# OpAmp.net
KiCad netlist of a schematic drawn in Altium Designer
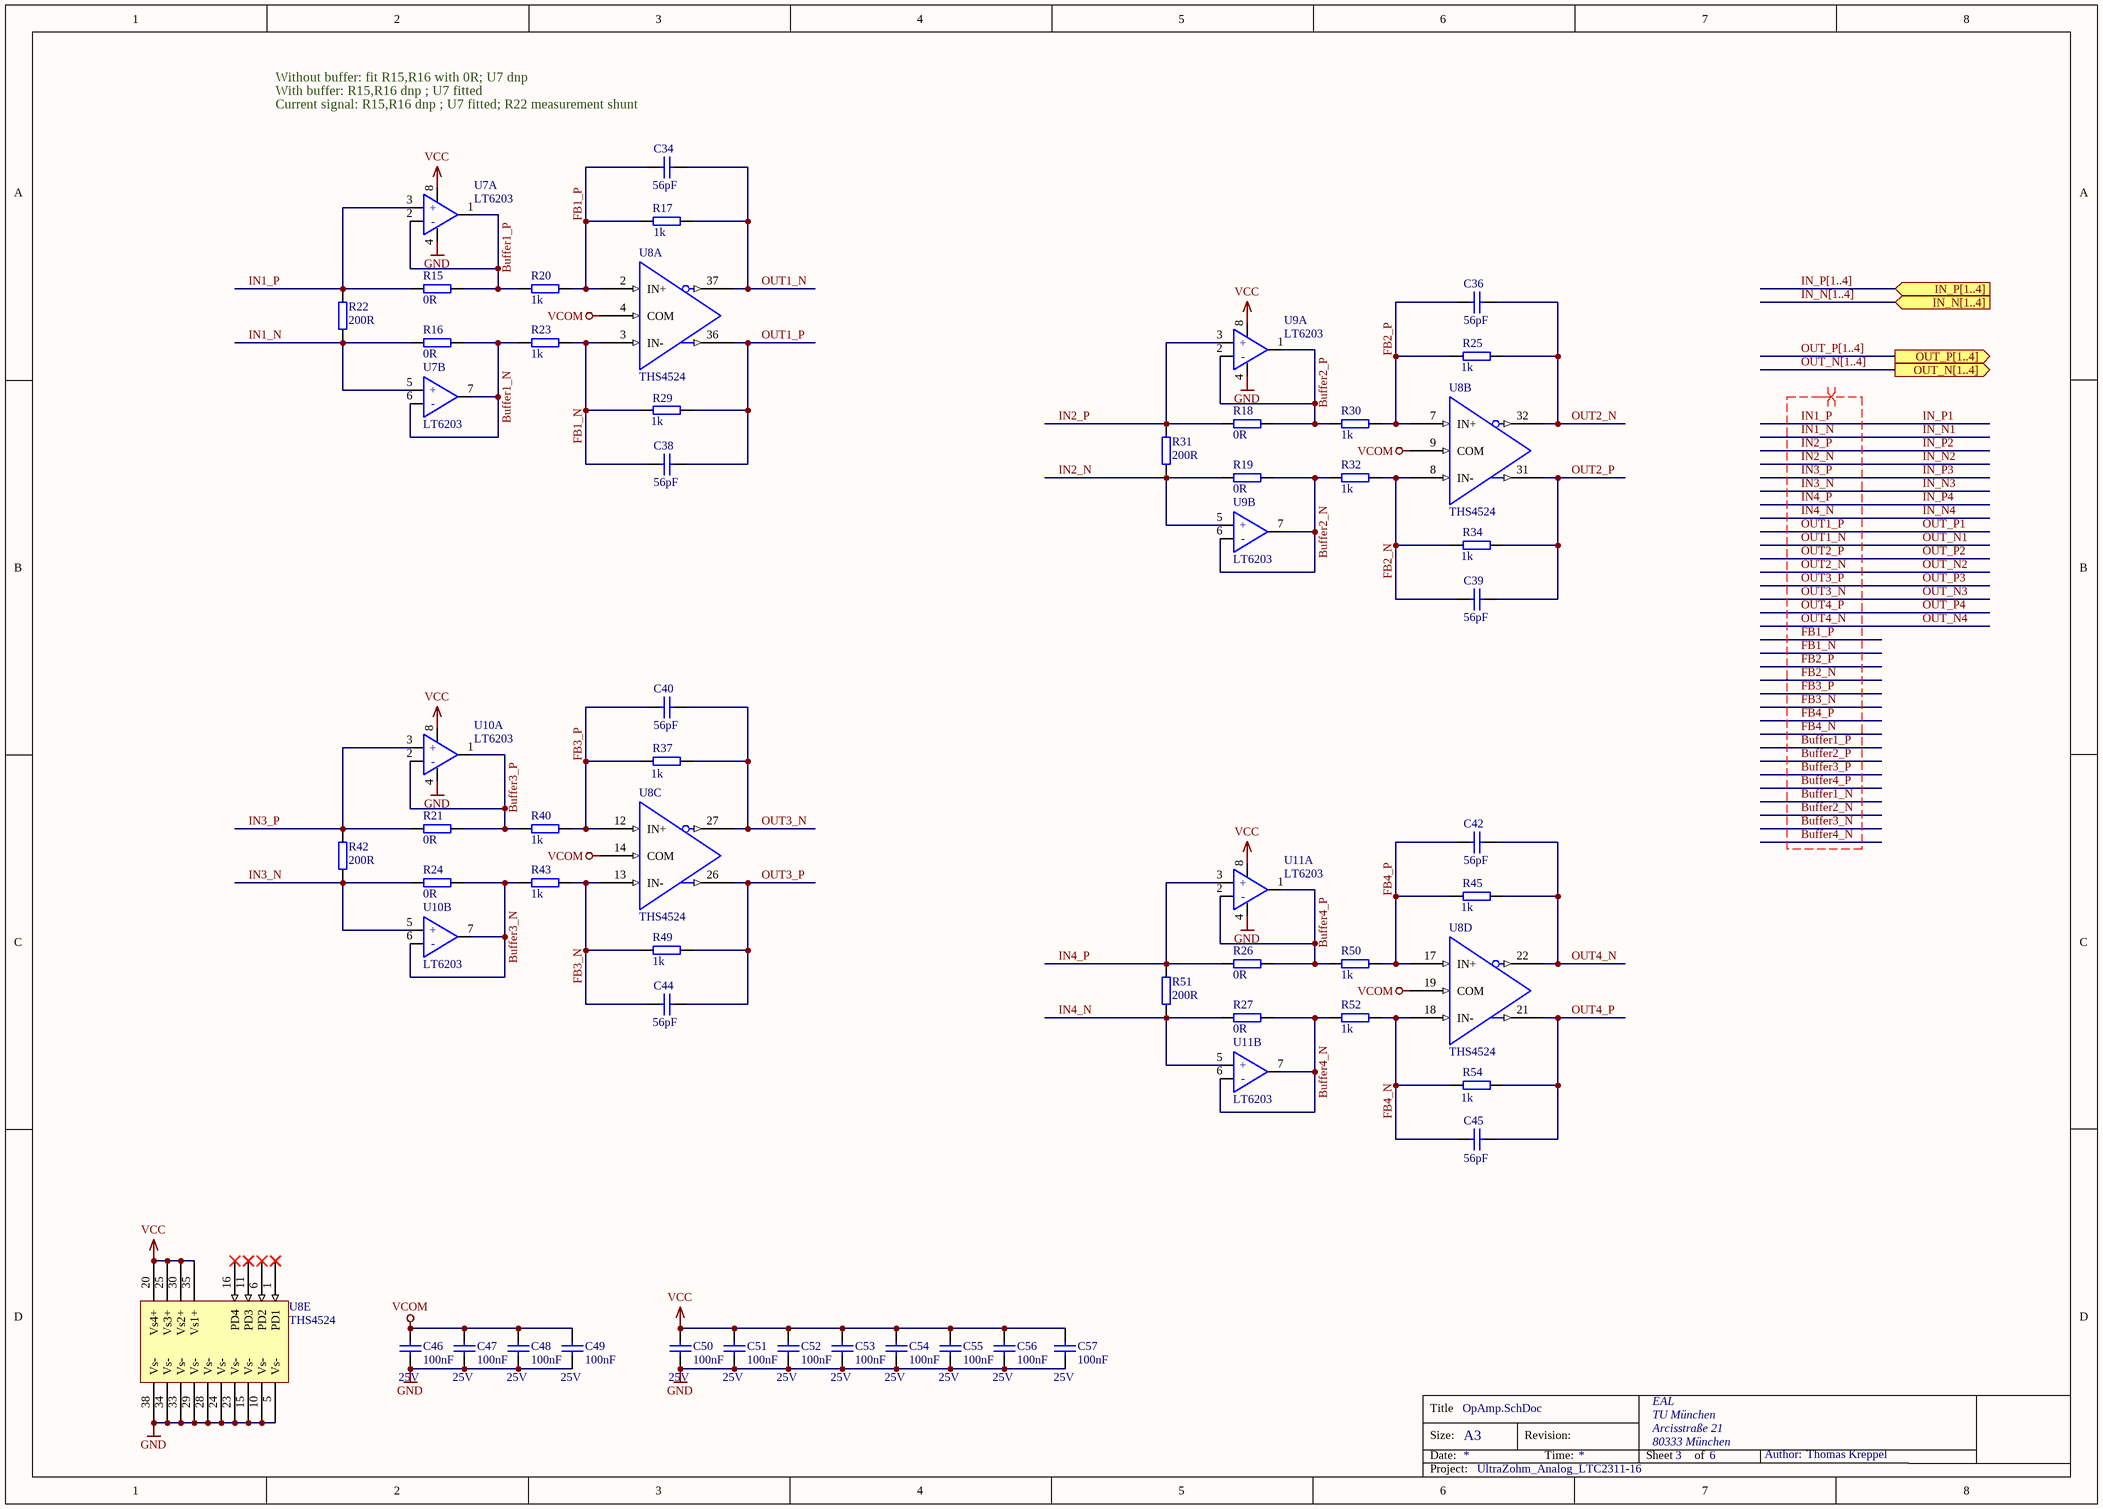
[diagram p0: OpAmp.SchDoc]

(export (version "E")
  (design (tool "Eeschema 10.0.6"))
  (components
    (comp (ref "C34")
      (value "56pF")
      (footprint "CAPC1608X07N")
      (fields
        (field (name "MF") "Vishay")
        (field (name "MPN") "VJ0603A560JXACW1BC")
        (field (name "VOLTAGE") "50V")
      )
      (libsource (lib "UltraZohm_ADC") (part "Cap_0603"))
    )
    (comp (ref "C36")
      (value "56pF")
      (footprint "CAPC1608X07N")
      (fields
        (field (name "MF") "Vishay")
        (field (name "MPN") "VJ0603A560JXACW1BC")
        (field (name "VOLTAGE") "50V")
      )
      (libsource (lib "UltraZohm_ADC") (part "Cap_0603"))
    )
    (comp (ref "C38")
      (value "56pF")
      (footprint "CAPC1608X07N")
      (fields
        (field (name "MF") "Vishay")
        (field (name "MPN") "VJ0603A560JXACW1BC")
        (field (name "VOLTAGE") "50V")
      )
      (libsource (lib "UltraZohm_ADC") (part "Cap_0603"))
    )
    (comp (ref "C39")
      (value "56pF")
      (footprint "CAPC1608X07N")
      (fields
        (field (name "MF") "Vishay")
        (field (name "MPN") "VJ0603A560JXACW1BC")
        (field (name "VOLTAGE") "50V")
      )
      (libsource (lib "UltraZohm_ADC") (part "Cap_0603"))
    )
    (comp (ref "C40")
      (value "56pF")
      (footprint "CAPC1608X07N")
      (fields
        (field (name "MF") "Vishay")
        (field (name "MPN") "VJ0603A560JXACW1BC")
        (field (name "VOLTAGE") "50V")
      )
      (libsource (lib "UltraZohm_ADC") (part "Cap_0603"))
    )
    (comp (ref "C42")
      (value "56pF")
      (footprint "CAPC1608X07N")
      (fields
        (field (name "MF") "Vishay")
        (field (name "MPN") "VJ0603A560JXACW1BC")
        (field (name "VOLTAGE") "50V")
      )
      (libsource (lib "UltraZohm_ADC") (part "Cap_0603"))
    )
    (comp (ref "C44")
      (value "56pF")
      (footprint "CAPC1608X07N")
      (fields
        (field (name "MF") "Vishay")
        (field (name "MPN") "VJ0603A560JXACW1BC")
        (field (name "VOLTAGE") "50V")
      )
      (libsource (lib "UltraZohm_ADC") (part "Cap_0603"))
    )
    (comp (ref "C45")
      (value "56pF")
      (footprint "CAPC1608X07N")
      (fields
        (field (name "MF") "Vishay")
        (field (name "MPN") "VJ0603A560JXACW1BC")
        (field (name "VOLTAGE") "50V")
      )
      (libsource (lib "UltraZohm_ADC") (part "Cap_0603"))
    )
    (comp (ref "C46")
      (value "100nF")
      (footprint "CAPC1608X07N")
      (fields (field (name "MF") "Würth") (field (name "MPN") "885012206071") (field (name "VOLTAGE") "25V"))
      (libsource (lib "UltraZohm_ADC") (part "Cap_0603"))
    )
    (comp (ref "C47")
      (value "100nF")
      (footprint "CAPC1608X07N")
      (fields (field (name "MF") "Würth") (field (name "MPN") "885012206071") (field (name "VOLTAGE") "25V"))
      (libsource (lib "UltraZohm_ADC") (part "Cap_0603"))
    )
    (comp (ref "C48")
      (value "100nF")
      (footprint "CAPC1608X07N")
      (fields (field (name "MF") "Würth") (field (name "MPN") "885012206071") (field (name "VOLTAGE") "25V"))
      (libsource (lib "UltraZohm_ADC") (part "Cap_0603"))
    )
    (comp (ref "C49")
      (value "100nF")
      (footprint "CAPC1608X07N")
      (fields (field (name "MF") "Würth") (field (name "MPN") "885012206071") (field (name "VOLTAGE") "25V"))
      (libsource (lib "UltraZohm_ADC") (part "Cap_0603"))
    )
    (comp (ref "C50")
      (value "100nF")
      (footprint "CAPC1608X07N")
      (fields (field (name "MF") "Würth") (field (name "MPN") "885012206071") (field (name "VOLTAGE") "25V"))
      (libsource (lib "UltraZohm_ADC") (part "Cap_0603"))
    )
    (comp (ref "C51")
      (value "100nF")
      (footprint "CAPC1608X07N")
      (fields (field (name "MF") "Würth") (field (name "MPN") "885012206071") (field (name "VOLTAGE") "25V"))
      (libsource (lib "UltraZohm_ADC") (part "Cap_0603"))
    )
    (comp (ref "C52")
      (value "100nF")
      (footprint "CAPC1608X07N")
      (fields (field (name "MF") "Würth") (field (name "MPN") "885012206071") (field (name "VOLTAGE") "25V"))
      (libsource (lib "UltraZohm_ADC") (part "Cap_0603"))
    )
    (comp (ref "C53")
      (value "100nF")
      (footprint "CAPC1608X07N")
      (fields (field (name "MF") "Würth") (field (name "MPN") "885012206071") (field (name "VOLTAGE") "25V"))
      (libsource (lib "UltraZohm_ADC") (part "Cap_0603"))
    )
    (comp (ref "C54")
      (value "100nF")
      (footprint "CAPC1608X07N")
      (fields (field (name "MF") "Würth") (field (name "MPN") "885012206071") (field (name "VOLTAGE") "25V"))
      (libsource (lib "UltraZohm_ADC") (part "Cap_0603"))
    )
    (comp (ref "C55")
      (value "100nF")
      (footprint "CAPC1608X07N")
      (fields (field (name "MF") "Würth") (field (name "MPN") "885012206071") (field (name "VOLTAGE") "25V"))
      (libsource (lib "UltraZohm_ADC") (part "Cap_0603"))
    )
    (comp (ref "C56")
      (value "100nF")
      (footprint "CAPC1608X07N")
      (fields (field (name "MF") "Würth") (field (name "MPN") "885012206071") (field (name "VOLTAGE") "25V"))
      (libsource (lib "UltraZohm_ADC") (part "Cap_0603"))
    )
    (comp (ref "C57")
      (value "100nF")
      (footprint "CAPC1608X07N")
      (fields (field (name "MF") "Würth") (field (name "MPN") "885012206071") (field (name "VOLTAGE") "25V"))
      (libsource (lib "UltraZohm_ADC") (part "Cap_0603"))
    )
    (comp (ref "R15")
      (value "0R")
      (footprint "RESC1608X06N")
      (fields (field (name "MF") "Vishay / Dale") (field (name "MPN") "CRCW06030000Z0EBC"))
      (libsource (lib "UltraZohm_ADC") (part "R_0603"))
    )
    (comp (ref "R16")
      (value "0R")
      (footprint "RESC1608X06N")
      (fields (field (name "MF") "Vishay / Dale") (field (name "MPN") "CRCW06030000Z0EBC"))
      (libsource (lib "UltraZohm_ADC") (part "R_0603"))
    )
    (comp (ref "R17")
      (value "1k")
      (footprint "RESC1608X06N")
      (fields (field (name "MF") "Vishay / Dale") (field (name "MPN") "CRCW06031K00JNEAC"))
      (libsource (lib "UltraZohm_ADC") (part "R_0603"))
    )
    (comp (ref "R18")
      (value "0R")
      (footprint "RESC1608X06N")
      (fields (field (name "MF") "Vishay / Dale") (field (name "MPN") "CRCW06030000Z0EBC"))
      (libsource (lib "UltraZohm_ADC") (part "R_0603"))
    )
    (comp (ref "R19")
      (value "0R")
      (footprint "RESC1608X06N")
      (fields (field (name "MF") "Vishay / Dale") (field (name "MPN") "CRCW06030000Z0EBC"))
      (libsource (lib "UltraZohm_ADC") (part "R_0603"))
    )
    (comp (ref "R20")
      (value "1k")
      (footprint "RESC1608X06N")
      (fields (field (name "MF") "Vishay / Dale") (field (name "MPN") "CRCW06031K00JNEAC"))
      (libsource (lib "UltraZohm_ADC") (part "R_0603"))
    )
    (comp (ref "R21")
      (value "0R")
      (footprint "RESC1608X06N")
      (fields (field (name "MF") "Vishay / Dale") (field (name "MPN") "CRCW06030000Z0EBC"))
      (libsource (lib "UltraZohm_ADC") (part "R_0603"))
    )
    (comp (ref "R22")
      (value "200R")
      (footprint "RESC3216X65N")
      (description "WID SMD 1M 5% 0,25W")
      (fields
        (field (name "TOLERANCE") "5%")
        (field (name "MF") "AECOL/Ohmite")
        (field (name "CREATED") "2018_07_20_AGeiger")
      )
      (libsource (lib "UltraZOhm_CarrierBoard") (part "R_1206"))
    )
    (comp (ref "R23")
      (value "1k")
      (footprint "RESC1608X06N")
      (fields (field (name "MF") "Vishay / Dale") (field (name "MPN") "CRCW06031K00JNEAC"))
      (libsource (lib "UltraZohm_ADC") (part "R_0603"))
    )
    (comp (ref "R24")
      (value "0R")
      (footprint "RESC1608X06N")
      (fields (field (name "MF") "Vishay / Dale") (field (name "MPN") "CRCW06030000Z0EBC"))
      (libsource (lib "UltraZohm_ADC") (part "R_0603"))
    )
    (comp (ref "R25")
      (value "1k")
      (footprint "RESC1608X06N")
      (fields (field (name "MF") "Vishay / Dale") (field (name "MPN") "CRCW06031K00JNEAC"))
      (libsource (lib "UltraZohm_ADC") (part "R_0603"))
    )
    (comp (ref "R26")
      (value "0R")
      (footprint "RESC1608X06N")
      (fields (field (name "MF") "Vishay / Dale") (field (name "MPN") "CRCW06030000Z0EBC"))
      (libsource (lib "UltraZohm_ADC") (part "R_0603"))
    )
    (comp (ref "R27")
      (value "0R")
      (footprint "RESC1608X06N")
      (fields (field (name "MF") "Vishay / Dale") (field (name "MPN") "CRCW06030000Z0EBC"))
      (libsource (lib "UltraZohm_ADC") (part "R_0603"))
    )
    (comp (ref "R29")
      (value "1k")
      (footprint "RESC1608X06N")
      (fields (field (name "MF") "Vishay / Dale") (field (name "MPN") "CRCW06031K00JNEAC"))
      (libsource (lib "UltraZohm_ADC") (part "R_0603"))
    )
    (comp (ref "R30")
      (value "1k")
      (footprint "RESC1608X06N")
      (fields (field (name "MF") "Vishay / Dale") (field (name "MPN") "CRCW06031K00JNEAC"))
      (libsource (lib "UltraZohm_ADC") (part "R_0603"))
    )
    (comp (ref "R31")
      (value "200R")
      (footprint "RESC3216X65N")
      (description "WID SMD 1M 5% 0,25W")
      (fields
        (field (name "TOLERANCE") "5%")
        (field (name "MF") "AECOL/Ohmite")
        (field (name "CREATED") "2018_07_20_AGeiger")
      )
      (libsource (lib "UltraZOhm_CarrierBoard") (part "R_1206"))
    )
    (comp (ref "R32")
      (value "1k")
      (footprint "RESC1608X06N")
      (fields (field (name "MF") "Vishay / Dale") (field (name "MPN") "CRCW06031K00JNEAC"))
      (libsource (lib "UltraZohm_ADC") (part "R_0603"))
    )
    (comp (ref "R34")
      (value "1k")
      (footprint "RESC1608X06N")
      (fields (field (name "MF") "Vishay / Dale") (field (name "MPN") "CRCW06031K00JNEAC"))
      (libsource (lib "UltraZohm_ADC") (part "R_0603"))
    )
    (comp (ref "R37")
      (value "1k")
      (footprint "RESC1608X06N")
      (fields (field (name "MF") "Vishay / Dale") (field (name "MPN") "CRCW06031K00JNEAC"))
      (libsource (lib "UltraZohm_ADC") (part "R_0603"))
    )
    (comp (ref "R40")
      (value "1k")
      (footprint "RESC1608X06N")
      (fields (field (name "MF") "Vishay / Dale") (field (name "MPN") "CRCW06031K00JNEAC"))
      (libsource (lib "UltraZohm_ADC") (part "R_0603"))
    )
    (comp (ref "R42")
      (value "200R")
      (footprint "RESC3216X65N")
      (description "WID SMD 1M 5% 0,25W")
      (fields
        (field (name "TOLERANCE") "5%")
        (field (name "MF") "AECOL/Ohmite")
        (field (name "CREATED") "2018_07_20_AGeiger")
      )
      (libsource (lib "UltraZOhm_CarrierBoard") (part "R_1206"))
    )
    (comp (ref "R43")
      (value "1k")
      (footprint "RESC1608X06N")
      (fields (field (name "MF") "Vishay / Dale") (field (name "MPN") "CRCW06031K00JNEAC"))
      (libsource (lib "UltraZohm_ADC") (part "R_0805"))
    )
    (comp (ref "R45")
      (value "1k")
      (footprint "RESC1608X06N")
      (fields (field (name "MF") "Vishay / Dale") (field (name "MPN") "CRCW06031K00JNEAC"))
      (libsource (lib "UltraZohm_ADC") (part "R_0603"))
    )
    (comp (ref "R49")
      (value "1k")
      (footprint "RESC1608X06N")
      (fields (field (name "MF") "Vishay / Dale") (field (name "MPN") "CRCW06031K00JNEAC"))
      (libsource (lib "UltraZohm_ADC") (part "R_0603"))
    )
    (comp (ref "R50")
      (value "1k")
      (footprint "RESC1608X06N")
      (fields (field (name "MF") "Vishay / Dale") (field (name "MPN") "CRCW06031K00JNEAC"))
      (libsource (lib "UltraZohm_ADC") (part "R_0603"))
    )
    (comp (ref "R51")
      (value "200R")
      (footprint "RESC3216X65N")
      (description "WID SMD 1M 5% 0,25W")
      (fields
        (field (name "TOLERANCE") "5%")
        (field (name "MF") "AECOL/Ohmite")
        (field (name "CREATED") "2018_07_20_AGeiger")
      )
      (libsource (lib "UltraZOhm_CarrierBoard") (part "R_1206"))
    )
    (comp (ref "R52")
      (value "1k")
      (footprint "RESC1608X06N")
      (fields (field (name "MF") "Vishay / Dale") (field (name "MPN") "CRCW06031K00JNEAC"))
      (libsource (lib "UltraZohm_ADC") (part "R_0603"))
    )
    (comp (ref "R54")
      (value "1k")
      (footprint "RESC1608X06N")
      (fields (field (name "MF") "Vishay / Dale") (field (name "MPN") "CRCW06031K00JNEAC"))
      (libsource (lib "UltraZohm_ADC") (part "R_0603"))
    )
    (comp (ref "U7")
      (value "LT6203")
      (footprint "MSOP8_3x3-8N")
      (description "2 Ch Low Noise, Low Power OpAmp")
      (fields
        (field (name "MF") "Linear Technology")
        (field (name "MPN") "LT6203CMS8#PBF")
        (field (name "CREATED") "Kreppel_20190830")
      )
      (libsource (lib "UltraZohm_ADC") (part "LT6203_MSOP8"))
    )
    (comp (ref "U8")
      (value "THS4524")
      (footprint "THS4524 Footprint")
      (description "Quad Channel fully differential Amplilfier")
      (fields (field (name "MF") "Texas Instruments") (field (name "CREATED") "20190720_Kreppel"))
      (libsource (lib "") (part "THS4524_1"))
    )
    (comp (ref "U9")
      (value "LT6203")
      (footprint "MSOP8_3x3-8N")
      (description "2 Ch Low Noise, Low Power OpAmp")
      (fields
        (field (name "MF") "Linear Technology")
        (field (name "MPN") "LT6203CMS8#PBF")
        (field (name "CREATED") "Kreppel_20190830")
      )
      (libsource (lib "UltraZohm_ADC") (part "LT6203_MSOP8"))
    )
    (comp (ref "U10")
      (value "LT6203")
      (footprint "MSOP8_3x3-8N")
      (description "2 Ch Low Noise, Low Power OpAmp")
      (fields
        (field (name "MF") "Linear Technology")
        (field (name "MPN") "LT6203CMS8#PBF")
        (field (name "CREATED") "Kreppel_20190830")
      )
      (libsource (lib "UltraZohm_ADC") (part "LT6203_MSOP8"))
    )
    (comp (ref "U11")
      (value "LT6203")
      (footprint "MSOP8_3x3-8N")
      (description "2 Ch Low Noise, Low Power OpAmp")
      (fields
        (field (name "MF") "Linear Technology")
        (field (name "MPN") "LT6203CMS8#PBF")
        (field (name "CREATED") "Kreppel_20190830")
      )
      (libsource (lib "UltraZohm_ADC") (part "LT6203_MSOP8"))
    )
  )
  (nets
    (net (code "1") (name "/Buffer1_N") (class "Default")
      (node (ref "R16") (pin "2") (pintype "passive"))
      (node (ref "R23") (pin "2") (pintype "passive"))
      (node (ref "U7") (pin "6") (pinfunction "-_6") (pintype "passive"))
      (node (ref "U7") (pin "7") (pintype "passive"))
    )
    (net (code "2") (name "/Buffer1_P") (class "Default")
      (node (ref "R15") (pin "2") (pintype "passive"))
      (node (ref "R20") (pin "1") (pintype "passive"))
      (node (ref "U7") (pin "1") (pintype "passive"))
      (node (ref "U7") (pin "2") (pinfunction "-_2") (pintype "passive"))
    )
    (net (code "3") (name "/Buffer2_N") (class "Default")
      (node (ref "R19") (pin "2") (pintype "passive"))
      (node (ref "R32") (pin "2") (pintype "passive"))
      (node (ref "U9") (pin "6") (pinfunction "-_6") (pintype "passive"))
      (node (ref "U9") (pin "7") (pintype "passive"))
    )
    (net (code "4") (name "/Buffer2_P") (class "Default")
      (node (ref "R18") (pin "2") (pintype "passive"))
      (node (ref "R30") (pin "1") (pintype "passive"))
      (node (ref "U9") (pin "1") (pintype "passive"))
      (node (ref "U9") (pin "2") (pinfunction "-_2") (pintype "passive"))
    )
    (net (code "5") (name "/Buffer3_N") (class "Default")
      (node (ref "R24") (pin "2") (pintype "passive"))
      (node (ref "R43") (pin "2") (pintype "passive"))
      (node (ref "U10") (pin "6") (pinfunction "-_6") (pintype "passive"))
      (node (ref "U10") (pin "7") (pintype "passive"))
    )
    (net (code "6") (name "/Buffer3_P") (class "Default")
      (node (ref "R21") (pin "2") (pintype "passive"))
      (node (ref "R40") (pin "1") (pintype "passive"))
      (node (ref "U10") (pin "1") (pintype "passive"))
      (node (ref "U10") (pin "2") (pinfunction "-_2") (pintype "passive"))
    )
    (net (code "7") (name "/Buffer4_N") (class "Default")
      (node (ref "R27") (pin "2") (pintype "passive"))
      (node (ref "R52") (pin "2") (pintype "passive"))
      (node (ref "U11") (pin "6") (pinfunction "-_6") (pintype "passive"))
      (node (ref "U11") (pin "7") (pintype "passive"))
    )
    (net (code "8") (name "/Buffer4_P") (class "Default")
      (node (ref "R26") (pin "2") (pintype "passive"))
      (node (ref "R50") (pin "1") (pintype "passive"))
      (node (ref "U11") (pin "1") (pintype "passive"))
      (node (ref "U11") (pin "2") (pinfunction "-_2") (pintype "passive"))
    )
    (net (code "9") (name "/FB1_N") (class "Default")
      (node (ref "C38") (pin "1") (pinfunction "1_1") (pintype "passive"))
      (node (ref "R23") (pin "1") (pintype "passive"))
      (node (ref "R29") (pin "1") (pintype "passive"))
      (node (ref "U8") (pin "3") (pinfunction "IN-_3") (pintype "input"))
    )
    (net (code "10") (name "/FB1_P") (class "Default")
      (node (ref "C34") (pin "1") (pinfunction "1_1") (pintype "passive"))
      (node (ref "R17") (pin "1") (pintype "passive"))
      (node (ref "R20") (pin "2") (pintype "passive"))
      (node (ref "U8") (pin "2") (pinfunction "IN+_2") (pintype "input"))
    )
    (net (code "11") (name "/FB2_N") (class "Default")
      (node (ref "C39") (pin "1") (pinfunction "1_1") (pintype "passive"))
      (node (ref "R32") (pin "1") (pintype "passive"))
      (node (ref "R34") (pin "1") (pintype "passive"))
      (node (ref "U8") (pin "8") (pinfunction "IN-_8") (pintype "input"))
    )
    (net (code "12") (name "/FB2_P") (class "Default")
      (node (ref "C36") (pin "1") (pinfunction "1_1") (pintype "passive"))
      (node (ref "R25") (pin "1") (pintype "passive"))
      (node (ref "R30") (pin "2") (pintype "passive"))
      (node (ref "U8") (pin "7") (pinfunction "IN+_7") (pintype "input"))
    )
    (net (code "13") (name "/FB3_N") (class "Default")
      (node (ref "C44") (pin "1") (pinfunction "1_1") (pintype "passive"))
      (node (ref "R43") (pin "1") (pintype "passive"))
      (node (ref "R49") (pin "1") (pintype "passive"))
      (node (ref "U8") (pin "13") (pinfunction "IN-_13") (pintype "input"))
    )
    (net (code "14") (name "/FB3_P") (class "Default")
      (node (ref "C40") (pin "1") (pinfunction "1_1") (pintype "passive"))
      (node (ref "R37") (pin "1") (pintype "passive"))
      (node (ref "R40") (pin "2") (pintype "passive"))
      (node (ref "U8") (pin "12") (pinfunction "IN+_12") (pintype "input"))
    )
    (net (code "15") (name "/FB4_N") (class "Default")
      (node (ref "C45") (pin "1") (pinfunction "1_1") (pintype "passive"))
      (node (ref "R52") (pin "1") (pintype "passive"))
      (node (ref "R54") (pin "1") (pintype "passive"))
      (node (ref "U8") (pin "18") (pinfunction "IN-_18") (pintype "input"))
    )
    (net (code "16") (name "/FB4_P") (class "Default")
      (node (ref "C42") (pin "1") (pinfunction "1_1") (pintype "passive"))
      (node (ref "R45") (pin "1") (pintype "passive"))
      (node (ref "R50") (pin "2") (pintype "passive"))
      (node (ref "U8") (pin "17") (pinfunction "IN+_17") (pintype "input"))
    )
    (net (code "17") (name "/IN_N1") (class "Default")
      (node (ref "R16") (pin "1") (pintype "passive"))
      (node (ref "R22") (pin "1") (pinfunction "1_1") (pintype "passive"))
      (node (ref "U7") (pin "5") (pinfunction "+_5") (pintype "passive"))
    )
    (net (code "18") (name "/IN_N2") (class "Default")
      (node (ref "R19") (pin "1") (pintype "passive"))
      (node (ref "R31") (pin "1") (pinfunction "1_1") (pintype "passive"))
      (node (ref "U9") (pin "5") (pinfunction "+_5") (pintype "passive"))
    )
    (net (code "19") (name "/IN_N3") (class "Default")
      (node (ref "R24") (pin "1") (pintype "passive"))
      (node (ref "R42") (pin "1") (pinfunction "1_1") (pintype "passive"))
      (node (ref "U10") (pin "5") (pinfunction "+_5") (pintype "passive"))
    )
    (net (code "20") (name "/IN_N4") (class "Default")
      (node (ref "R27") (pin "1") (pintype "passive"))
      (node (ref "R51") (pin "1") (pinfunction "1_1") (pintype "passive"))
      (node (ref "U11") (pin "5") (pinfunction "+_5") (pintype "passive"))
    )
    (net (code "22") (name "/IN_P1") (class "Default")
      (node (ref "R15") (pin "1") (pintype "passive"))
      (node (ref "R22") (pin "2") (pinfunction "2_2") (pintype "passive"))
      (node (ref "U7") (pin "3") (pinfunction "+_3") (pintype "passive"))
    )
    (net (code "23") (name "/IN_P2") (class "Default")
      (node (ref "R18") (pin "1") (pintype "passive"))
      (node (ref "R31") (pin "2") (pinfunction "2_2") (pintype "passive"))
      (node (ref "U9") (pin "3") (pinfunction "+_3") (pintype "passive"))
    )
    (net (code "24") (name "/IN_P3") (class "Default")
      (node (ref "R21") (pin "1") (pintype "passive"))
      (node (ref "R42") (pin "2") (pinfunction "2_2") (pintype "passive"))
      (node (ref "U10") (pin "3") (pinfunction "+_3") (pintype "passive"))
    )
    (net (code "25") (name "/IN_P4") (class "Default")
      (node (ref "R26") (pin "1") (pintype "passive"))
      (node (ref "R51") (pin "2") (pinfunction "2_2") (pintype "passive"))
      (node (ref "U11") (pin "3") (pinfunction "+_3") (pintype "passive"))
    )
    (net (code "27") (name "/OUT_N1") (class "Default")
      (node (ref "C34") (pin "2") (pinfunction "2_2") (pintype "passive"))
      (node (ref "R17") (pin "2") (pintype "passive"))
      (node (ref "U8") (pin "37") (pinfunction "OUT-_37") (pintype "output"))
    )
    (net (code "28") (name "/OUT_N2") (class "Default")
      (node (ref "C36") (pin "2") (pinfunction "2_2") (pintype "passive"))
      (node (ref "R25") (pin "2") (pintype "passive"))
      (node (ref "U8") (pin "32") (pinfunction "OUT-_32") (pintype "output"))
    )
    (net (code "29") (name "/OUT_N3") (class "Default")
      (node (ref "C40") (pin "2") (pinfunction "2_2") (pintype "passive"))
      (node (ref "R37") (pin "2") (pintype "passive"))
      (node (ref "U8") (pin "27") (pinfunction "OUT-_27") (pintype "output"))
    )
    (net (code "30") (name "/OUT_N4") (class "Default")
      (node (ref "C42") (pin "2") (pinfunction "2_2") (pintype "passive"))
      (node (ref "R45") (pin "2") (pintype "passive"))
      (node (ref "U8") (pin "22") (pinfunction "OUT-_22") (pintype "output"))
    )
    (net (code "32") (name "/OUT_P1") (class "Default")
      (node (ref "C38") (pin "2") (pinfunction "2_2") (pintype "passive"))
      (node (ref "R29") (pin "2") (pintype "passive"))
      (node (ref "U8") (pin "36") (pinfunction "OUT+_36") (pintype "output"))
    )
    (net (code "33") (name "/OUT_P2") (class "Default")
      (node (ref "C39") (pin "2") (pinfunction "2_2") (pintype "passive"))
      (node (ref "R34") (pin "2") (pintype "passive"))
      (node (ref "U8") (pin "31") (pinfunction "OUT+_31") (pintype "output"))
    )
    (net (code "34") (name "/OUT_P3") (class "Default")
      (node (ref "C44") (pin "2") (pinfunction "2_2") (pintype "passive"))
      (node (ref "R49") (pin "2") (pintype "passive"))
      (node (ref "U8") (pin "26") (pinfunction "OUT+_26") (pintype "output"))
    )
    (net (code "35") (name "/OUT_P4") (class "Default")
      (node (ref "C45") (pin "2") (pinfunction "2_2") (pintype "passive"))
      (node (ref "R54") (pin "2") (pintype "passive"))
      (node (ref "U8") (pin "21") (pinfunction "OUT+_21") (pintype "output"))
    )
    (net (code "37") (name "GND") (class "Default")
      (node (ref "C46") (pin "2") (pinfunction "2_2") (pintype "passive"))
      (node (ref "C47") (pin "2") (pinfunction "2_2") (pintype "passive"))
      (node (ref "C48") (pin "2") (pinfunction "2_2") (pintype "passive"))
      (node (ref "C49") (pin "2") (pinfunction "2_2") (pintype "passive"))
      (node (ref "C50") (pin "2") (pinfunction "2_2") (pintype "passive"))
      (node (ref "C51") (pin "2") (pinfunction "2_2") (pintype "passive"))
      (node (ref "C52") (pin "2") (pinfunction "2_2") (pintype "passive"))
      (node (ref "C53") (pin "2") (pinfunction "2_2") (pintype "passive"))
      (node (ref "C54") (pin "2") (pinfunction "2_2") (pintype "passive"))
      (node (ref "C55") (pin "2") (pinfunction "2_2") (pintype "passive"))
      (node (ref "C56") (pin "2") (pinfunction "2_2") (pintype "passive"))
      (node (ref "C57") (pin "2") (pinfunction "2_2") (pintype "passive"))
      (node (ref "U10") (pin "4") (pintype "passive"))
      (node (ref "U11") (pin "4") (pintype "passive"))
      (node (ref "U7") (pin "4") (pintype "passive"))
      (node (ref "U8") (pin "10") (pinfunction "Vs-_10") (pintype "power_in"))
      (node (ref "U8") (pin "15") (pinfunction "Vs-_15") (pintype "passive"))
      (node (ref "U8") (pin "23") (pinfunction "Vs-_23") (pintype "power_in"))
      (node (ref "U8") (pin "24") (pinfunction "Vs-_24") (pintype "power_in"))
      (node (ref "U8") (pin "28") (pinfunction "Vs-_28") (pintype "power_in"))
      (node (ref "U8") (pin "29") (pinfunction "Vs-_29") (pintype "power_in"))
      (node (ref "U8") (pin "33") (pinfunction "Vs-_33") (pintype "power_in"))
      (node (ref "U8") (pin "34") (pinfunction "Vs-_34") (pintype "power_in"))
      (node (ref "U8") (pin "38") (pinfunction "Vs-_38") (pintype "power_in"))
      (node (ref "U8") (pin "5") (pinfunction "Vs-_5") (pintype "power_in"))
      (node (ref "U9") (pin "4") (pintype "passive"))
    )
    (net (code "38") (name "VCC") (class "Default")
      (node (ref "C50") (pin "1") (pinfunction "1_1") (pintype "passive"))
      (node (ref "C51") (pin "1") (pinfunction "1_1") (pintype "passive"))
      (node (ref "C52") (pin "1") (pinfunction "1_1") (pintype "passive"))
      (node (ref "C53") (pin "1") (pinfunction "1_1") (pintype "passive"))
      (node (ref "C54") (pin "1") (pinfunction "1_1") (pintype "passive"))
      (node (ref "C55") (pin "1") (pinfunction "1_1") (pintype "passive"))
      (node (ref "C56") (pin "1") (pinfunction "1_1") (pintype "passive"))
      (node (ref "C57") (pin "1") (pinfunction "1_1") (pintype "passive"))
      (node (ref "U10") (pin "8") (pintype "passive"))
      (node (ref "U11") (pin "8") (pintype "passive"))
      (node (ref "U7") (pin "8") (pintype "passive"))
      (node (ref "U8") (pin "20") (pinfunction "Vs4+_20") (pintype "power_in"))
      (node (ref "U8") (pin "25") (pinfunction "Vs3+_25") (pintype "power_in"))
      (node (ref "U8") (pin "30") (pinfunction "Vs2+_30") (pintype "power_in"))
      (node (ref "U8") (pin "35") (pinfunction "Vs1+_35") (pintype "power_in"))
      (node (ref "U9") (pin "8") (pintype "passive"))
    )
    (net (code "39") (name "VCOM") (class "Default")
      (node (ref "C46") (pin "1") (pinfunction "1_1") (pintype "passive"))
      (node (ref "C47") (pin "1") (pinfunction "1_1") (pintype "passive"))
      (node (ref "C48") (pin "1") (pinfunction "1_1") (pintype "passive"))
      (node (ref "C49") (pin "1") (pinfunction "1_1") (pintype "passive"))
      (node (ref "U8") (pin "14") (pinfunction "COM_14") (pintype "input"))
      (node (ref "U8") (pin "19") (pinfunction "COM_19") (pintype "input"))
      (node (ref "U8") (pin "4") (pinfunction "COM_4") (pintype "input"))
      (node (ref "U8") (pin "9") (pinfunction "COM_9") (pintype "input"))
    )
    (net (code "40") (name "unconnected-(U8E-PD1-Pad1)") (class "Default")
      (node (ref "U8") (pin "1") (pinfunction "PD1_1") (pintype "input+no_connect"))
    )
    (net (code "41") (name "unconnected-(U8E-PD2-Pad6)") (class "Default")
      (node (ref "U8") (pin "6") (pinfunction "PD2_6") (pintype "input+no_connect"))
    )
    (net (code "42") (name "unconnected-(U8E-PD3-Pad11)") (class "Default")
      (node (ref "U8") (pin "11") (pinfunction "PD3_11") (pintype "input+no_connect"))
    )
    (net (code "43") (name "unconnected-(U8E-PD4-Pad16)") (class "Default")
      (node (ref "U8") (pin "16") (pinfunction "PD4_16") (pintype "input+no_connect"))
    )
  )
)
